# power.net
KiCad netlist of a schematic drawn in Altium Designer
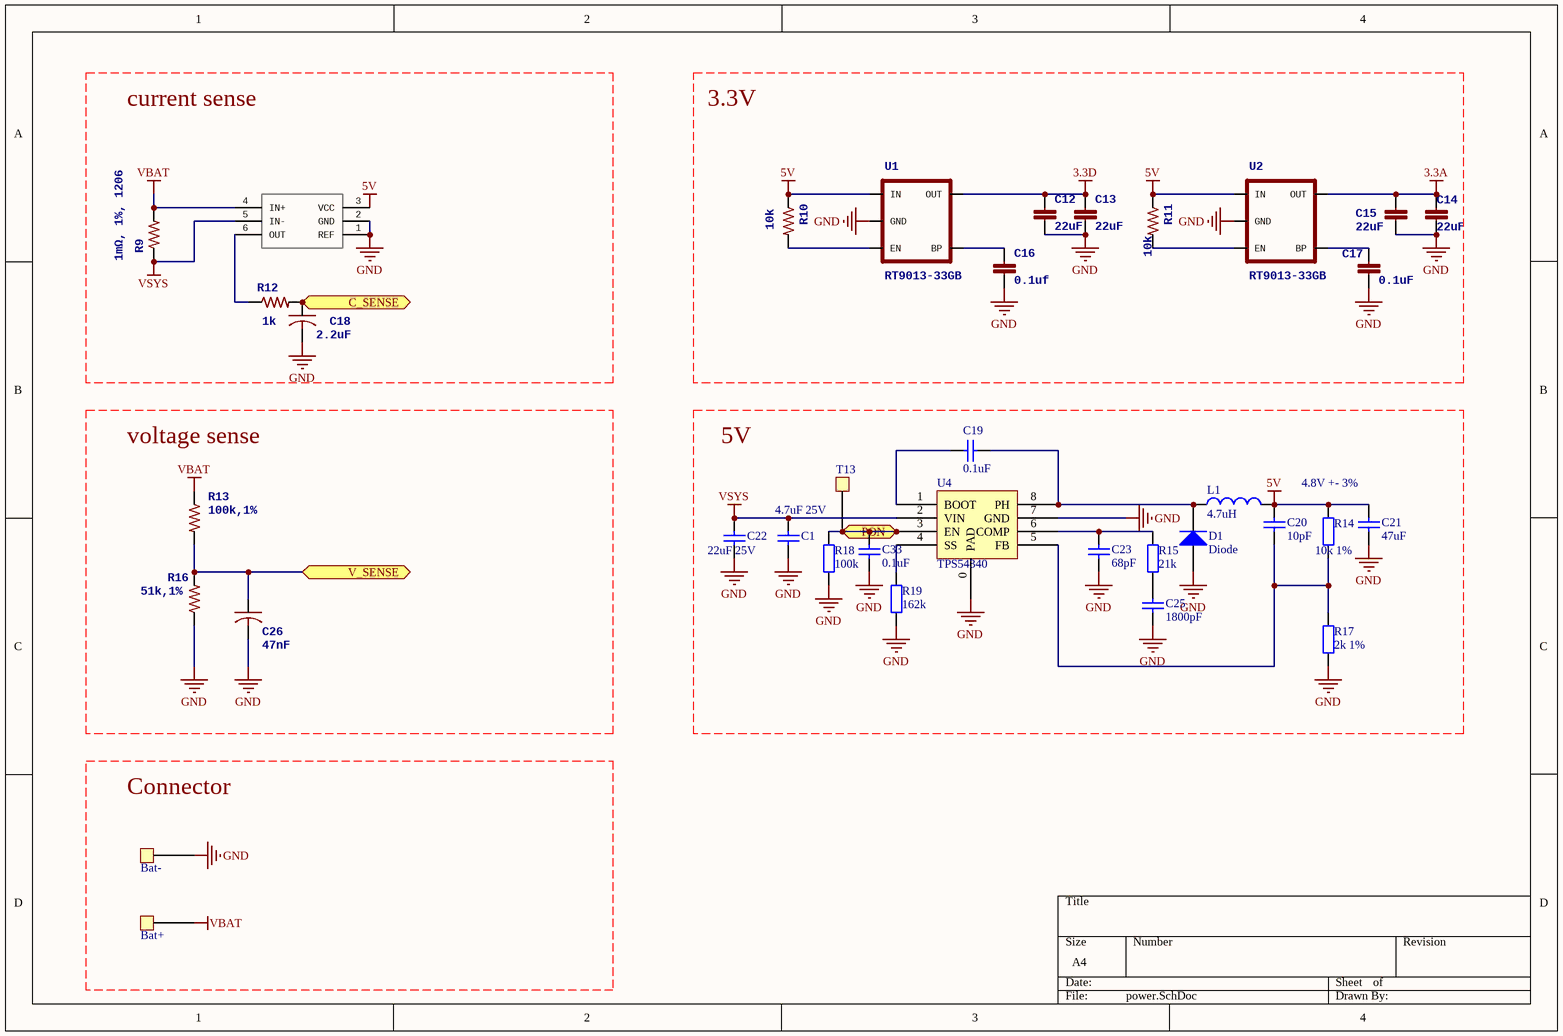
[diagram p0: power.SchDoc]

(export (version "E")
  (design (tool "Eeschema 10.0.6"))
  (components
    (comp (ref "Bat+") (value "TestPad") (footprint "BatteryHole") (libsource (lib "sch") (part "TestPad")))
    (comp (ref "Bat-") (value "TestPad") (footprint "BatteryHole") (libsource (lib "sch") (part "TestPad")))
    (comp (ref "C1")
      (value "4.7uF 25V")
      (footprint "0805")
      (description "Capacitor")
      (fields (field (name "Comment") "Cap") (field (name "PUBLISHER") "Altium Limited"))
      (libsource (lib "RTC6705") (part "Cap"))
    )
    (comp (ref "C12")
      (value "22uF")
      (footprint "0805")
      (description "<b>Capacitor</b>\nStandard 0603 ceramic capacitor, and 0.1\" leaded capacitor.")
      (fields (field (name "PARTNO") "CC0402ZRY5V7BB104"))
      (libsource (lib "pixhawk2") (part "CAP0402-CAP"))
    )
    (comp (ref "C13")
      (value "22uF")
      (footprint "0805")
      (description "<b>Capacitor</b>\nStandard 0603 ceramic capacitor, and 0.1\" leaded capacitor.")
      (fields (field (name "PARTNO") "CC0402ZRY5V7BB104"))
      (libsource (lib "pixhawk2") (part "CAP0402-CAP"))
    )
    (comp (ref "C14")
      (value "22uF")
      (footprint "0805")
      (description "<b>Capacitor</b>\nStandard 0603 ceramic capacitor, and 0.1\" leaded capacitor.")
      (fields (field (name "PARTNO") "CC0402ZRY5V7BB104"))
      (libsource (lib "pixhawk2") (part "CAP0402-CAP"))
    )
    (comp (ref "C15")
      (value "22uF")
      (footprint "0805")
      (description "<b>Capacitor</b>\nStandard 0603 ceramic capacitor, and 0.1\" leaded capacitor.")
      (fields (field (name "PARTNO") "CC0402ZRY5V7BB104"))
      (libsource (lib "pixhawk2") (part "CAP0402-CAP"))
    )
    (comp (ref "C16")
      (value "0.1uf")
      (footprint "0402")
      (description "<b>Capacitor</b>\nStandard 0603 ceramic capacitor, and 0.1\" leaded capacitor.")
      (fields (field (name "PARTNO") "CC0402ZRY5V7BB104"))
      (libsource (lib "pixhawk2") (part "CAP0402-CAP"))
    )
    (comp (ref "C17")
      (value "0.1uF")
      (footprint "0402")
      (description "<b>Capacitor</b>\nStandard 0603 ceramic capacitor, and 0.1\" leaded capacitor.")
      (fields (field (name "PARTNO") "CC0402ZRY5V7BB104"))
      (libsource (lib "pixhawk2") (part "CAP0402-CAP"))
    )
    (comp (ref "C18")
      (value "2.2uF")
      (footprint "0402")
      (description "<B>CAPACITOR</B>, American symbol")
      (libsource (lib "adafruit") (part "C-USC0402"))
    )
    (comp (ref "C19")
      (value "0.1uF")
      (footprint "0402")
      (description "Capacitor")
      (fields (field (name "Comment") "Cap") (field (name "PUBLISHER") "Altium Limited"))
      (libsource (lib "RTC6705") (part "Cap"))
    )
    (comp (ref "C20")
      (value "10pF")
      (footprint "0402")
      (description "Capacitor")
      (fields (field (name "Comment") "Cap") (field (name "PUBLISHER") "Altium Limited"))
      (libsource (lib "RTC6705") (part "Cap"))
    )
    (comp (ref "C21")
      (value "47uF")
      (footprint "1210")
      (description "Capacitor")
      (fields (field (name "Comment") "Cap") (field (name "PUBLISHER") "Altium Limited"))
      (libsource (lib "RTC6705") (part "Cap"))
    )
    (comp (ref "C22")
      (value "22uF 25V")
      (footprint "1210")
      (description "Capacitor")
      (fields (field (name "Comment") "Cap") (field (name "PUBLISHER") "Altium Limited"))
      (libsource (lib "RTC6705") (part "Cap"))
    )
    (comp (ref "C23")
      (value "68pF")
      (footprint "0402")
      (description "Capacitor")
      (fields (field (name "Comment") "Cap") (field (name "PUBLISHER") "Altium Limited"))
      (libsource (lib "RTC6705") (part "Cap"))
    )
    (comp (ref "C25")
      (value "1800pF")
      (footprint "0402")
      (description "Capacitor")
      (fields (field (name "Comment") "Cap") (field (name "PUBLISHER") "Altium Limited"))
      (libsource (lib "RTC6705") (part "Cap"))
    )
    (comp (ref "C26")
      (value "47nF")
      (footprint "0402")
      (description "<B>CAPACITOR</B>, American symbol")
      (libsource (lib "adafruit") (part "C-USC0402"))
    )
    (comp (ref "C33")
      (value "0.1uF")
      (footprint "0402")
      (description "Capacitor")
      (fields (field (name "Comment") "Cap") (field (name "PUBLISHER") "Altium Limited"))
      (libsource (lib "RTC6705") (part "Cap"))
    )
    (comp (ref "D1")
      (value "Diode")
      (footprint "LC-SMB(DO-214AA)_S1")
      (description "Default Diode")
      (fields (field (name "PUBLISHER") "Altium Limited"))
      (libsource (lib "Miscellaneous Devices") (part "Diode"))
    )
    (comp (ref "L1")
      (value "4.7uH")
      (footprint "L7022")
      (description "Inductor")
      (fields (field (name "PUBLISHER") "Altium Limited"))
      (libsource (lib "Miscellaneous Devices") (part "Inductor"))
    )
    (comp (ref "R9")
      (value "1mΩ, 1%, 1206")
      (footprint "1206")
      (libsource (lib "SparkFun") (part "CSS2725FTL250"))
    )
    (comp (ref "R10")
      (value "10k")
      (footprint "0402")
      (description "<b>Resistor</b>\nBasic schematic elements and footprints for 0603, 1206, and PTH resistors.")
      (libsource (lib "SparkFun") (part "RESISTOR0402-RES"))
    )
    (comp (ref "R11")
      (value "10k")
      (footprint "0402")
      (description "<b>Resistor</b>\nBasic schematic elements and footprints for 0603, 1206, and PTH resistors.")
      (libsource (lib "SparkFun") (part "RESISTOR0402-RES"))
    )
    (comp (ref "R12")
      (value "1k")
      (footprint "0402")
      (description "<b>Resistor</b>\nBasic schematic elements and footprints for 0603, 1206, and PTH resistors.")
      (libsource (lib "SparkFun") (part "RESISTOR0402-RES"))
    )
    (comp (ref "R13")
      (value "100k,1%")
      (footprint "0402")
      (description "<b>Resistor</b>\nBasic schematic elements and footprints for 0603, 1206, and PTH resistors.")
      (libsource (lib "SparkFun") (part "RESISTOR0402-RES"))
    )
    (comp (ref "R14")
      (value "10k 1%")
      (footprint "0402")
      (description "Resistor")
      (fields (field (name "Comment") "Res2") (field (name "PUBLISHER") "Altium Limited"))
      (libsource (lib "RTC6705") (part "Res2"))
    )
    (comp (ref "R15")
      (value "21k")
      (footprint "0402")
      (description "Resistor")
      (fields (field (name "Comment") "Res2") (field (name "PUBLISHER") "Altium Limited"))
      (libsource (lib "RTC6705") (part "Res2"))
    )
    (comp (ref "R16")
      (value "51k,1%")
      (footprint "0402")
      (description "<b>Resistor</b>\nBasic schematic elements and footprints for 0603, 1206, and PTH resistors.")
      (libsource (lib "SparkFun") (part "RESISTOR0402-RES"))
    )
    (comp (ref "R17")
      (value "2k 1%")
      (footprint "0402")
      (description "Resistor")
      (fields (field (name "Comment") "Res2") (field (name "PUBLISHER") "Altium Limited"))
      (libsource (lib "RTC6705") (part "Res2"))
    )
    (comp (ref "R18")
      (value "100k")
      (footprint "0402")
      (description "Resistor")
      (fields (field (name "Comment") "Res2") (field (name "PUBLISHER") "Altium Limited"))
      (libsource (lib "RTC6705") (part "Res2"))
    )
    (comp (ref "R19")
      (value "162k")
      (footprint "0402")
      (description "Resistor")
      (fields (field (name "Comment") "Res2") (field (name "PUBLISHER") "Altium Limited"))
      (libsource (lib "RTC6705") (part "Res2"))
    )
    (comp (ref "T13") (value "TestPad") (footprint "TestPad - 1mm") (libsource (lib "") (part "TestPad_1")))
    (comp (ref "U1")
      (value "RT9013-33GB")
      (footprint "SOT23-5")
      (fields (field (name "PARTNO") "MIC5207-3.3YM5"))
      (libsource (lib "pixhawk2") (part "V_REG_LDOSMD"))
    )
    (comp (ref "U2")
      (value "RT9013-33GB")
      (footprint "SOT23-5")
      (fields (field (name "PARTNO") "MIC5207-3.3YM5"))
      (libsource (lib "pixhawk2") (part "V_REG_LDOSMD"))
    )
    (comp (ref "U4") (value "TPS54340") (footprint "D8-Pad") (libsource (lib "sch") (part "TPS54340")))
    (comp (ref "U6")
      (value "INA199")
      (footprint "LC-SC-70-6(SOT-363)")
      (libsource (lib "sch") (part "INA199"))
    )
  )
  (nets
    (net (code "1") (name "/C_SENSE") (class "Default")
      (node (ref "C18") (pin "1") (pinfunction "1_1") (pintype "passive"))
      (node (ref "R12") (pin "2") (pinfunction "2_2") (pintype "passive"))
    )
    (net (code "2") (name "/PON") (class "Default")
      (node (ref "C33") (pin "1") (pinfunction "1_1") (pintype "passive"))
      (node (ref "R18") (pin "1") (pinfunction "1_1") (pintype "passive"))
      (node (ref "T13") (pin "1") (pinfunction "3_1") (pintype "passive"))
      (node (ref "U4") (pin "3") (pinfunction "EN_3") (pintype "passive"))
    )
    (net (code "3") (name "/V_SENSE") (class "Default")
      (node (ref "C26") (pin "1") (pinfunction "1_1") (pintype "passive"))
      (node (ref "R13") (pin "2") (pinfunction "2_2") (pintype "passive"))
      (node (ref "R16") (pin "2") (pinfunction "2_2") (pintype "passive"))
    )
    (net (code "4") (name "3.3A") (class "Default")
      (node (ref "C14") (pin "1") (pinfunction "1_1") (pintype "passive"))
      (node (ref "C15") (pin "1") (pinfunction "1_1") (pintype "passive"))
      (node (ref "U2") (pin "5") (pinfunction "OUT_5") (pintype "passive"))
    )
    (net (code "5") (name "3.3D") (class "Default")
      (node (ref "C12") (pin "1") (pinfunction "1_1") (pintype "passive"))
      (node (ref "C13") (pin "1") (pinfunction "1_1") (pintype "passive"))
      (node (ref "U1") (pin "5") (pinfunction "OUT_5") (pintype "passive"))
    )
    (net (code "6") (name "5V") (class "Default")
      (node (ref "C20") (pin "1") (pinfunction "1_1") (pintype "passive"))
      (node (ref "C21") (pin "1") (pinfunction "1_1") (pintype "passive"))
      (node (ref "L1") (pin "2") (pinfunction "2_2") (pintype "passive"))
      (node (ref "R10") (pin "1") (pinfunction "1_1") (pintype "passive"))
      (node (ref "R11") (pin "1") (pinfunction "1_1") (pintype "passive"))
      (node (ref "R14") (pin "1") (pinfunction "1_1") (pintype "passive"))
      (node (ref "U1") (pin "1") (pinfunction "IN_1") (pintype "passive"))
      (node (ref "U2") (pin "1") (pinfunction "IN_1") (pintype "passive"))
      (node (ref "U6") (pin "3") (pinfunction "VCC_3") (pintype "passive"))
    )
    (net (code "7") (name "GND") (class "Default")
      (node (ref "Bat-") (pin "1") (pinfunction "3_1") (pintype "passive"))
      (node (ref "C1") (pin "2") (pinfunction "2_2") (pintype "passive"))
      (node (ref "C12") (pin "2") (pinfunction "2_2") (pintype "passive"))
      (node (ref "C13") (pin "2") (pinfunction "2_2") (pintype "passive"))
      (node (ref "C14") (pin "2") (pinfunction "2_2") (pintype "passive"))
      (node (ref "C15") (pin "2") (pinfunction "2_2") (pintype "passive"))
      (node (ref "C16") (pin "2") (pinfunction "2_2") (pintype "passive"))
      (node (ref "C17") (pin "2") (pinfunction "2_2") (pintype "passive"))
      (node (ref "C18") (pin "2") (pinfunction "2_2") (pintype "passive"))
      (node (ref "C21") (pin "2") (pinfunction "2_2") (pintype "passive"))
      (node (ref "C22") (pin "2") (pinfunction "2_2") (pintype "passive"))
      (node (ref "C23") (pin "2") (pinfunction "2_2") (pintype "passive"))
      (node (ref "C25") (pin "2") (pinfunction "2_2") (pintype "passive"))
      (node (ref "C26") (pin "2") (pinfunction "2_2") (pintype "passive"))
      (node (ref "C33") (pin "2") (pinfunction "2_2") (pintype "passive"))
      (node (ref "D1") (pin "1") (pinfunction "A_1") (pintype "passive"))
      (node (ref "R16") (pin "1") (pinfunction "1_1") (pintype "passive"))
      (node (ref "R17") (pin "2") (pinfunction "2_2") (pintype "passive"))
      (node (ref "R18") (pin "2") (pinfunction "2_2") (pintype "passive"))
      (node (ref "R19") (pin "2") (pinfunction "2_2") (pintype "passive"))
      (node (ref "U1") (pin "2") (pinfunction "GND_2") (pintype "passive"))
      (node (ref "U2") (pin "2") (pinfunction "GND_2") (pintype "passive"))
      (node (ref "U4") (pin "0") (pinfunction "PAD_0") (pintype "passive"))
      (node (ref "U4") (pin "7") (pinfunction "GND_7") (pintype "passive"))
      (node (ref "U6") (pin "1") (pinfunction "REF_1") (pintype "passive"))
      (node (ref "U6") (pin "2") (pinfunction "GND_2") (pintype "passive"))
    )
    (net (code "8") (name "Net-(C25-Pad1)") (class "Default")
      (node (ref "C25") (pin "1") (pinfunction "1_1") (pintype "passive"))
      (node (ref "R15") (pin "2") (pinfunction "2_2") (pintype "passive"))
    )
    (net (code "9") (name "Net-(D1-K)") (class "Default")
      (node (ref "C19") (pin "1") (pinfunction "1_1") (pintype "passive"))
      (node (ref "D1") (pin "2") (pinfunction "K_2") (pintype "passive"))
      (node (ref "L1") (pin "1") (pinfunction "1_1") (pintype "passive"))
      (node (ref "U4") (pin "8") (pinfunction "PH_8") (pintype "passive"))
    )
    (net (code "10") (name "Net-(U1-BP)") (class "Default")
      (node (ref "C16") (pin "1") (pinfunction "1_1") (pintype "passive"))
      (node (ref "U1") (pin "4") (pinfunction "BP_4") (pintype "passive"))
    )
    (net (code "11") (name "Net-(U1-EN)") (class "Default")
      (node (ref "R10") (pin "2") (pinfunction "2_2") (pintype "passive"))
      (node (ref "U1") (pin "3") (pinfunction "EN_3") (pintype "passive"))
    )
    (net (code "12") (name "Net-(U2-BP)") (class "Default")
      (node (ref "C17") (pin "1") (pinfunction "1_1") (pintype "passive"))
      (node (ref "U2") (pin "4") (pinfunction "BP_4") (pintype "passive"))
    )
    (net (code "13") (name "Net-(U2-EN)") (class "Default")
      (node (ref "R11") (pin "2") (pinfunction "2_2") (pintype "passive"))
      (node (ref "U2") (pin "3") (pinfunction "EN_3") (pintype "passive"))
    )
    (net (code "14") (name "Net-(U4-BOOT)") (class "Default")
      (node (ref "C19") (pin "2") (pinfunction "2_2") (pintype "passive"))
      (node (ref "U4") (pin "1") (pinfunction "BOOT_1") (pintype "passive"))
    )
    (net (code "15") (name "Net-(U4-COMP)") (class "Default")
      (node (ref "C23") (pin "1") (pinfunction "1_1") (pintype "passive"))
      (node (ref "R15") (pin "1") (pinfunction "1_1") (pintype "passive"))
      (node (ref "U4") (pin "6") (pinfunction "COMP_6") (pintype "passive"))
    )
    (net (code "16") (name "Net-(U4-FB)") (class "Default")
      (node (ref "C20") (pin "2") (pinfunction "2_2") (pintype "passive"))
      (node (ref "R14") (pin "2") (pinfunction "2_2") (pintype "passive"))
      (node (ref "R17") (pin "1") (pinfunction "1_1") (pintype "passive"))
      (node (ref "U4") (pin "5") (pinfunction "FB_5") (pintype "passive"))
    )
    (net (code "17") (name "Net-(U4-SS)") (class "Default")
      (node (ref "R19") (pin "1") (pinfunction "1_1") (pintype "passive"))
      (node (ref "U4") (pin "4") (pinfunction "SS_4") (pintype "passive"))
    )
    (net (code "18") (name "Net-(U6-OUT)") (class "Default")
      (node (ref "R12") (pin "1") (pinfunction "1_1") (pintype "passive"))
      (node (ref "U6") (pin "6") (pinfunction "OUT_6") (pintype "passive"))
    )
    (net (code "19") (name "VBAT") (class "Default")
      (node (ref "Bat+") (pin "1") (pinfunction "3_1") (pintype "passive"))
      (node (ref "R13") (pin "1") (pinfunction "1_1") (pintype "passive"))
      (node (ref "R9") (pin "P$2") (pinfunction "2_P$2") (pintype "passive"))
      (node (ref "U6") (pin "4") (pinfunction "IN+_4") (pintype "passive"))
    )
    (net (code "20") (name "VSYS") (class "Default")
      (node (ref "C1") (pin "1") (pinfunction "1_1") (pintype "passive"))
      (node (ref "C22") (pin "1") (pinfunction "1_1") (pintype "passive"))
      (node (ref "R9") (pin "P$1") (pinfunction "1_P$1") (pintype "passive"))
      (node (ref "U4") (pin "2") (pinfunction "VIN_2") (pintype "passive"))
      (node (ref "U6") (pin "5") (pinfunction "IN-_5") (pintype "passive"))
    )
  )
)
